# design.net
KiCad netlist of a schematic drawn in Altium Designer
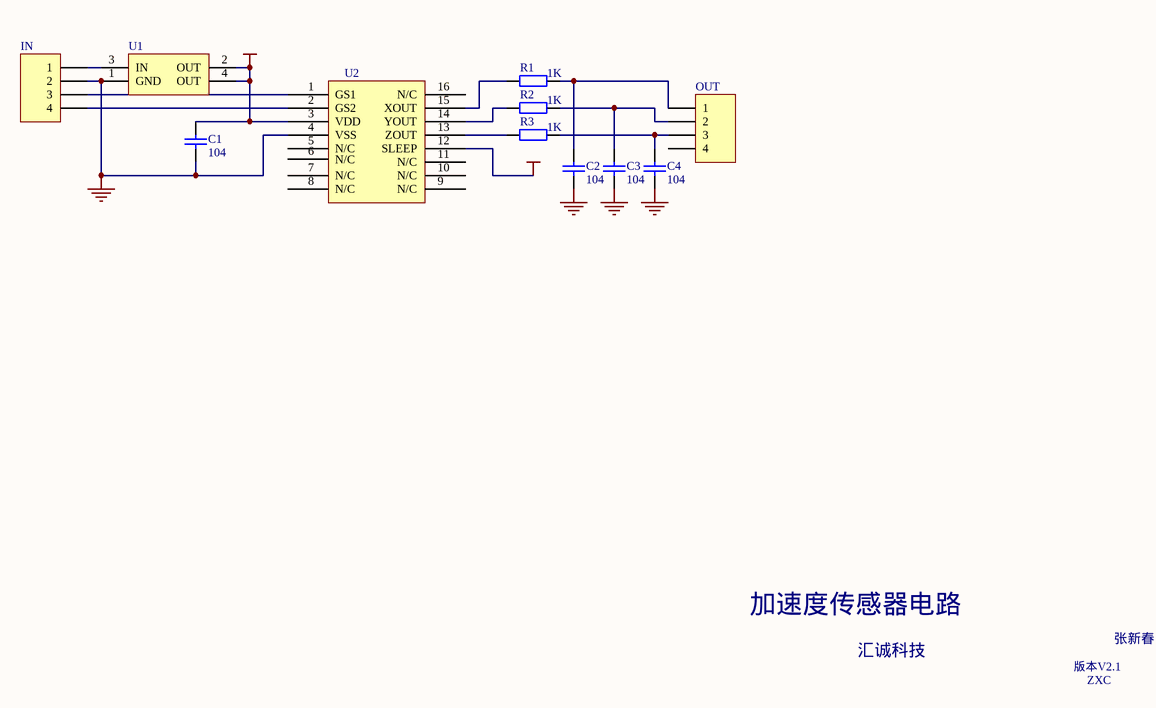
[diagram p0: 加速度传感器.SchDoc]

(export (version "E")
  (design (tool "Eeschema 10.0.6"))
  (components
    (comp (ref "C1")
      (value "104")
      (footprint "TP-0805-R")
      (description "瓷片电容")
      (fields (field (name "Comment") "CPDR") (field (name "PUBLISHER") "Altium Limited"))
      (libsource (lib "zxcourhc") (part "CPDR"))
    )
    (comp (ref "C2")
      (value "104")
      (footprint "TP-0805-R")
      (description "瓷片电容")
      (fields (field (name "Comment") "CPDR") (field (name "PUBLISHER") "Altium Limited"))
      (libsource (lib "zxcourhc") (part "CPDR"))
    )
    (comp (ref "C3")
      (value "104")
      (footprint "TP-0805-R")
      (description "瓷片电容")
      (fields (field (name "Comment") "CPDR") (field (name "PUBLISHER") "Altium Limited"))
      (libsource (lib "zxcourhc") (part "CPDR"))
    )
    (comp (ref "C4")
      (value "104")
      (footprint "TP-0805-R")
      (description "瓷片电容")
      (fields (field (name "Comment") "CPDR") (field (name "PUBLISHER") "Altium Limited"))
      (libsource (lib "zxcourhc") (part "CPDR"))
    )
    (comp (ref "IN")
      (value "PZ_4")
      (footprint "HDR-4")
      (description "排针——4")
      (fields (field (name "PUBLISHER") "Altium Limited"))
      (libsource (lib "zxcourhc") (part "PZ_4"))
    )
    (comp (ref "OUT")
      (value "PZ_4")
      (footprint "HDR-4")
      (description "排针——4")
      (fields (field (name "PUBLISHER") "Altium Limited"))
      (libsource (lib "加速度传感器") (part "PZ_4"))
    )
    (comp (ref "R1")
      (value "1K")
      (footprint "TP-0805-R")
      (description "电阻")
      (fields (field (name "Comment") "Res") (field (name "PUBLISHER") "Altium Limited"))
      (libsource (lib "zxcourhc") (part "Res"))
    )
    (comp (ref "R2")
      (value "1K")
      (footprint "TP-0805-R")
      (description "电阻")
      (fields (field (name "Comment") "Res") (field (name "PUBLISHER") "Altium Limited"))
      (libsource (lib "zxcourhc") (part "Res"))
    )
    (comp (ref "R3")
      (value "1K")
      (footprint "TP-0805-R")
      (description "电阻")
      (fields (field (name "Comment") "Res") (field (name "PUBLISHER") "Altium Limited"))
      (libsource (lib "zxcourhc") (part "Res"))
    )
    (comp (ref "U1")
      (value "REG1117-3.3")
      (footprint "ZZ311")
      (description "800mA and 1A Low Dropout Positive Regulator 2.85V, 3.3V, 5V, and Adjustable")
      (fields (field (name "PUBLISHER") "Altium Limited"))
      (libsource (lib "BB Power Mgt Voltage Regulator") (part "REG1117-5"))
    )
    (comp (ref "U2") (value "MMA7260") (footprint "A7260") (libsource (lib "zxcourhc") (part "MMA7260")))
  )
  (nets
    (net (code "1") (name "GND") (class "Default")
      (node (ref "C1") (pin "1") (pinfunction "1_1") (pintype "passive"))
      (node (ref "C2") (pin "1") (pinfunction "1_1") (pintype "passive"))
      (node (ref "C3") (pin "1") (pinfunction "1_1") (pintype "passive"))
      (node (ref "C4") (pin "1") (pinfunction "1_1") (pintype "passive"))
      (node (ref "IN") (pin "2") (pinfunction "2_2") (pintype "passive"))
      (node (ref "U1") (pin "1") (pinfunction "GND_1") (pintype "power_in"))
      (node (ref "U2") (pin "4") (pinfunction "VSS_4") (pintype "passive"))
    )
    (net (code "2") (name "Net-(C2-Pad2)") (class "Default")
      (node (ref "C2") (pin "2") (pinfunction "2_2") (pintype "passive"))
      (node (ref "OUT") (pin "1") (pinfunction "1_1") (pintype "passive"))
      (node (ref "R1") (pin "2") (pinfunction "2_2") (pintype "passive"))
    )
    (net (code "3") (name "Net-(C3-Pad2)") (class "Default")
      (node (ref "C3") (pin "2") (pinfunction "2_2") (pintype "passive"))
      (node (ref "OUT") (pin "2") (pinfunction "2_2") (pintype "passive"))
      (node (ref "R2") (pin "2") (pinfunction "2_2") (pintype "passive"))
    )
    (net (code "4") (name "Net-(C4-Pad2)") (class "Default")
      (node (ref "C4") (pin "2") (pinfunction "2_2") (pintype "passive"))
      (node (ref "OUT") (pin "3") (pinfunction "3_3") (pintype "passive"))
      (node (ref "R3") (pin "2") (pinfunction "2_2") (pintype "passive"))
    )
    (net (code "5") (name "Net-(U1-IN)") (class "Default")
      (node (ref "IN") (pin "1") (pinfunction "1_1") (pintype "passive"))
      (node (ref "U1") (pin "3") (pinfunction "IN_3") (pintype "power_in"))
    )
    (net (code "6") (name "Net-(U2-GS1)") (class "Default")
      (node (ref "IN") (pin "3") (pinfunction "3_3") (pintype "passive"))
      (node (ref "U2") (pin "1") (pinfunction "GS1_1") (pintype "passive"))
    )
    (net (code "7") (name "Net-(U2-GS2)") (class "Default")
      (node (ref "IN") (pin "4") (pinfunction "4_4") (pintype "passive"))
      (node (ref "U2") (pin "2") (pinfunction "GS2_2") (pintype "passive"))
    )
    (net (code "8") (name "Net-(U2-XOUT)") (class "Default")
      (node (ref "R1") (pin "1") (pinfunction "1_1") (pintype "passive"))
      (node (ref "U2") (pin "15") (pinfunction "XOUT_15") (pintype "passive"))
    )
    (net (code "9") (name "Net-(U2-YOUT)") (class "Default")
      (node (ref "R2") (pin "1") (pinfunction "1_1") (pintype "passive"))
      (node (ref "U2") (pin "14") (pinfunction "YOUT_14") (pintype "passive"))
    )
    (net (code "10") (name "Net-(U2-ZOUT)") (class "Default")
      (node (ref "R3") (pin "1") (pinfunction "1_1") (pintype "passive"))
      (node (ref "U2") (pin "13") (pinfunction "ZOUT_13") (pintype "passive"))
    )
    (net (code "11") (name "VCC") (class "Default")
      (node (ref "C1") (pin "2") (pinfunction "2_2") (pintype "passive"))
      (node (ref "U1") (pin "2") (pinfunction "OUT_2") (pintype "power_in"))
      (node (ref "U1") (pin "4") (pinfunction "OUT_4") (pintype "power_in"))
      (node (ref "U2") (pin "12") (pinfunction "SLEEP_12") (pintype "passive"))
      (node (ref "U2") (pin "3") (pinfunction "VDD_3") (pintype "passive"))
    )
    (net (code "12") (name "unconnected-(OUT-Pad4)") (class "Default")
      (node (ref "OUT") (pin "4") (pinfunction "4_4") (pintype "passive"))
    )
    (net (code "13") (name "unconnected-(U2-N{slash}C-Pad5)") (class "Default")
      (node (ref "U2") (pin "5") (pinfunction "N/C_5") (pintype "passive"))
    )
    (net (code "14") (name "unconnected-(U2-N{slash}C-Pad6)") (class "Default")
      (node (ref "U2") (pin "6") (pinfunction "N/C_6") (pintype "passive"))
    )
    (net (code "15") (name "unconnected-(U2-N{slash}C-Pad7)") (class "Default")
      (node (ref "U2") (pin "7") (pinfunction "N/C_7") (pintype "passive"))
    )
    (net (code "16") (name "unconnected-(U2-N{slash}C-Pad8)") (class "Default")
      (node (ref "U2") (pin "8") (pinfunction "N/C_8") (pintype "passive"))
    )
    (net (code "17") (name "unconnected-(U2-N{slash}C-Pad9)") (class "Default")
      (node (ref "U2") (pin "9") (pinfunction "N/C_9") (pintype "passive"))
    )
    (net (code "18") (name "unconnected-(U2-N{slash}C-Pad10)") (class "Default")
      (node (ref "U2") (pin "10") (pinfunction "N/C_10") (pintype "passive"))
    )
    (net (code "19") (name "unconnected-(U2-N{slash}C-Pad11)") (class "Default")
      (node (ref "U2") (pin "11") (pinfunction "N/C_11") (pintype "passive"))
    )
    (net (code "20") (name "unconnected-(U2-N{slash}C-Pad16)") (class "Default")
      (node (ref "U2") (pin "16") (pinfunction "N/C_16") (pintype "passive"))
    )
  )
)
